# Qi_Lime_Pi_Rev_1.net
KiCad netlist of a schematic drawn in EAGLE
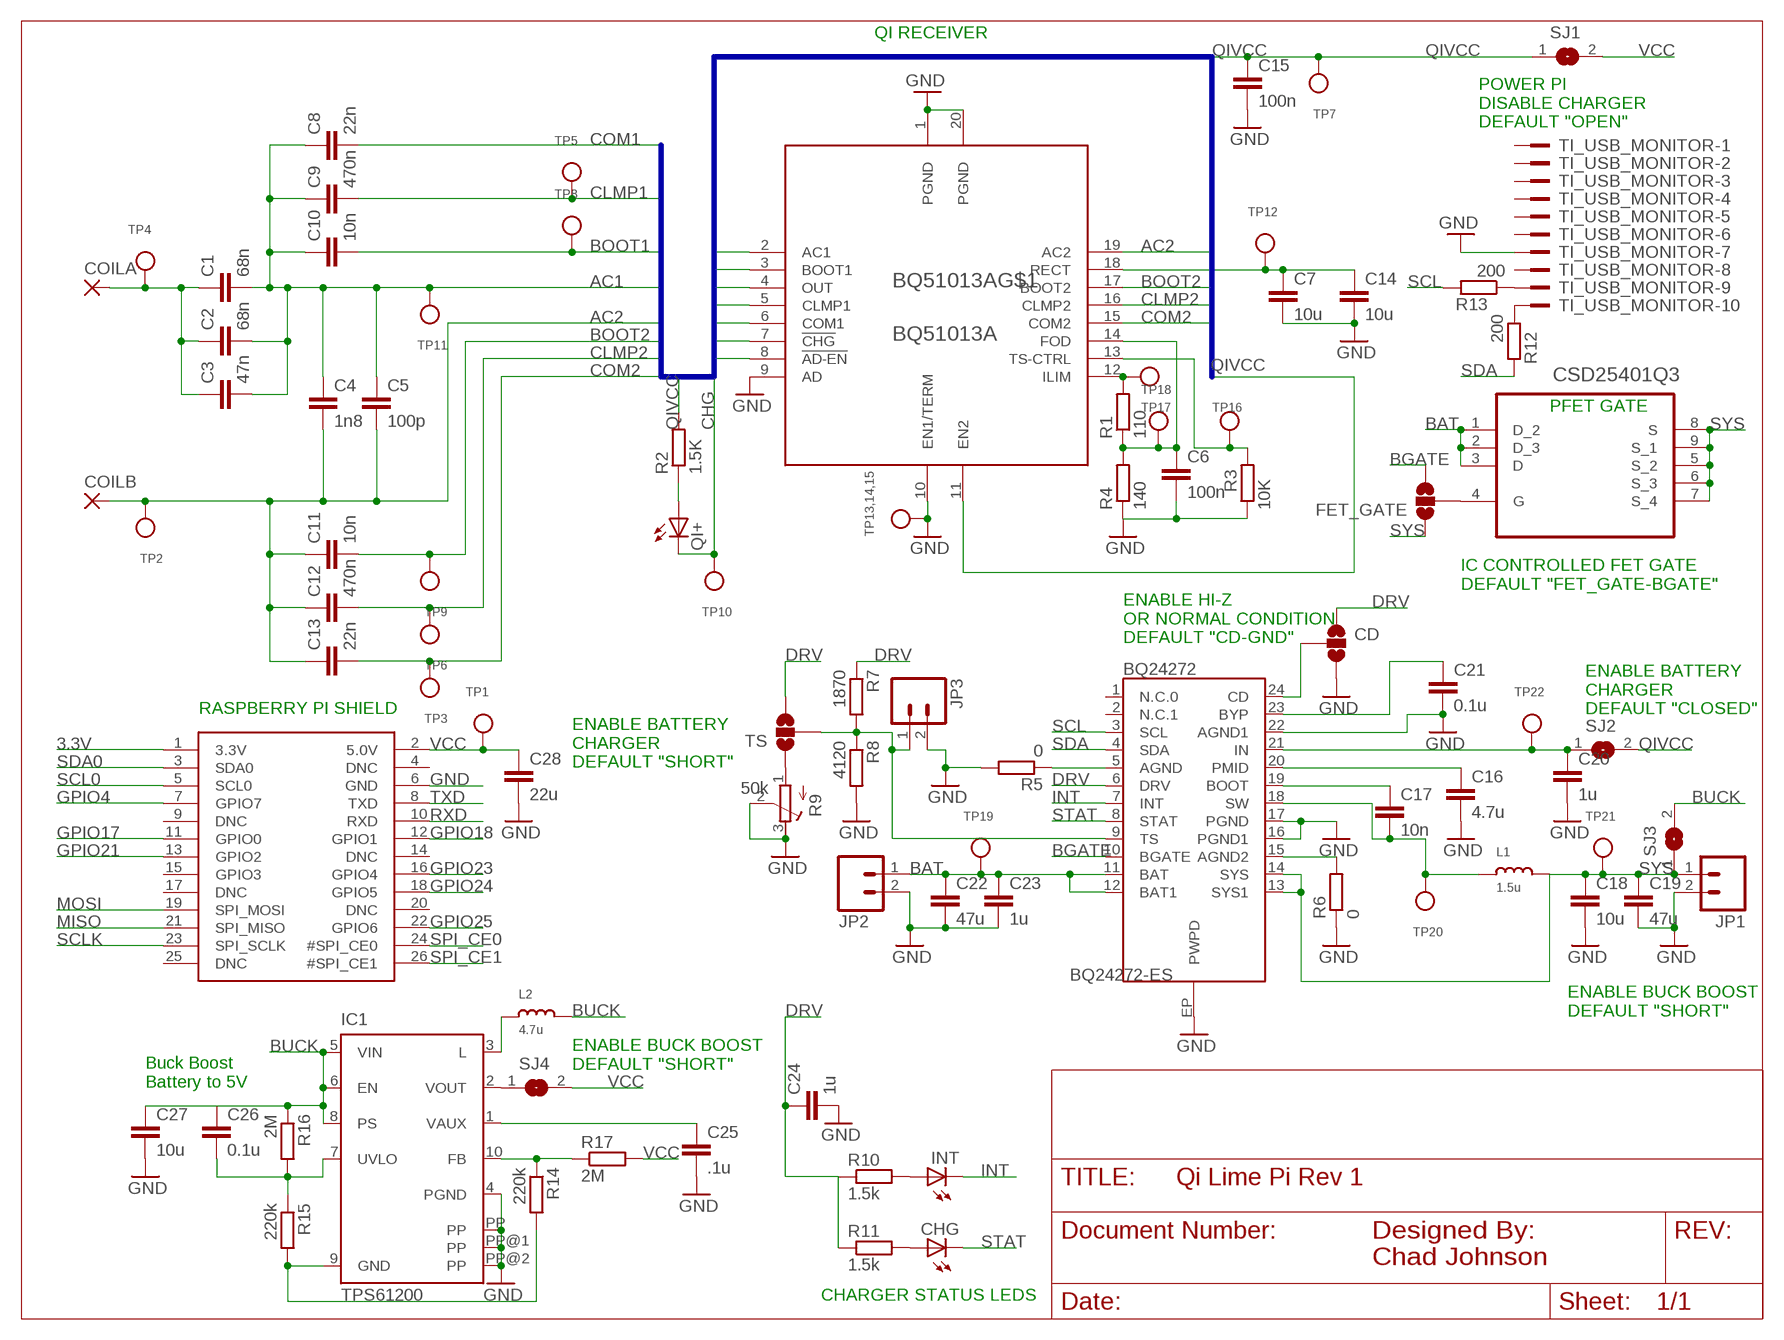
[diagram p0: schematic, sheet 1]

(export (version "E")
  (design (tool "Eeschema 10.0.6"))
  (components
    (comp (ref "BQ24272")
      (value "BQ24272-ES")
      (footprint "eagle-import:QFN-24_ALT2")
      (libsource (lib "eagle-import") (part "BQ24272-ES"))
    )
    (comp (ref "BQ51013A")
      (value "BQ51013A")
      (footprint "eagle-import:RHL_R-VQFN-N20")
      (libsource (lib "eagle-import") (part "BQ51013A"))
    )
    (comp (ref "C1")
      (value "68n")
      (footprint "eagle-import:C0603K")
      (fields (field (name "MF") "KEMET") (field (name "MPN") "C0603C682K5RACTU"))
      (libsource (lib "eagle-import") (part "C-EUC0603K"))
    )
    (comp (ref "C2")
      (value "68n")
      (footprint "eagle-import:C0603K")
      (fields (field (name "MF") "KEMET") (field (name "MPN") "C0603C682K5RACTU"))
      (libsource (lib "eagle-import") (part "C-EUC0603K"))
    )
    (comp (ref "C3")
      (value "47n")
      (footprint "eagle-import:C0603K")
      (fields (field (name "MPN") "C0603C473K5RACTU"))
      (libsource (lib "eagle-import") (part "C-EUC0603K"))
    )
    (comp (ref "C4")
      (value "1n8")
      (footprint "eagle-import:C0603K")
      (fields (field (name "MPN") "C0603C182K5RACTU"))
      (libsource (lib "eagle-import") (part "C-EUC0603K"))
    )
    (comp (ref "C5")
      (value "100p")
      (footprint "eagle-import:C0603K")
      (fields (field (name "MF") "KEMET") (field (name "MPN") "C0603C101K5RACTU"))
      (libsource (lib "eagle-import") (part "C-EUC0603K"))
    )
    (comp (ref "C6")
      (value "100n")
      (footprint "eagle-import:C0603K")
      (libsource (lib "eagle-import") (part "C-EUC0603K"))
    )
    (comp (ref "C7")
      (value "10u")
      (footprint "eagle-import:C0603K")
      (libsource (lib "eagle-import") (part "C-EUC0603K"))
    )
    (comp (ref "C8")
      (value "22n")
      (footprint "eagle-import:C0603K")
      (fields (field (name "MF") "KEMET") (field (name "MPN") "C0603C223K5RACTU"))
      (libsource (lib "eagle-import") (part "C-EUC0603K"))
    )
    (comp (ref "C9")
      (value "470n")
      (footprint "eagle-import:C0603K")
      (libsource (lib "eagle-import") (part "C-EUC0603K"))
    )
    (comp (ref "C10")
      (value "10n")
      (footprint "eagle-import:C0603K")
      (libsource (lib "eagle-import") (part "C-EUC0603K"))
    )
    (comp (ref "C11")
      (value "10n")
      (footprint "eagle-import:C0603K")
      (libsource (lib "eagle-import") (part "C-EUC0603K"))
    )
    (comp (ref "C12")
      (value "470n")
      (footprint "eagle-import:C0603K")
      (libsource (lib "eagle-import") (part "C-EUC0603K"))
    )
    (comp (ref "C13")
      (value "22n")
      (footprint "eagle-import:C0603K")
      (fields (field (name "MF") "KEMET") (field (name "MPN") "C0603C223K5RACTU"))
      (libsource (lib "eagle-import") (part "C-EUC0603K"))
    )
    (comp (ref "C14")
      (value "10u")
      (footprint "eagle-import:C0603K")
      (libsource (lib "eagle-import") (part "C-EUC0603K"))
    )
    (comp (ref "C15")
      (value "100n")
      (footprint "eagle-import:C0603K")
      (libsource (lib "eagle-import") (part "C-EUC0603K"))
    )
    (comp (ref "C16")
      (value "4.7u")
      (footprint "eagle-import:C0603K")
      (libsource (lib "eagle-import") (part "C-EUC0603K"))
    )
    (comp (ref "C17")
      (value "10n")
      (footprint "eagle-import:C0603K")
      (libsource (lib "eagle-import") (part "C-EUC0603K"))
    )
    (comp (ref "C18")
      (value "10u")
      (footprint "eagle-import:C0603K")
      (libsource (lib "eagle-import") (part "C-EUC0603K"))
    )
    (comp (ref "C19")
      (value "47u")
      (footprint "eagle-import:C0603K")
      (libsource (lib "eagle-import") (part "C-EUC0603K"))
    )
    (comp (ref "C20")
      (value "1u")
      (footprint "eagle-import:C0603K")
      (libsource (lib "eagle-import") (part "C-EUC0603K"))
    )
    (comp (ref "C21")
      (value "0.1u")
      (footprint "eagle-import:C0603K")
      (libsource (lib "eagle-import") (part "C-EUC0603K"))
    )
    (comp (ref "C22")
      (value "47u")
      (footprint "eagle-import:C0603K")
      (libsource (lib "eagle-import") (part "C-EUC0603K"))
    )
    (comp (ref "C23")
      (value "1u")
      (footprint "eagle-import:C0603K")
      (libsource (lib "eagle-import") (part "C-EUC0603K"))
    )
    (comp (ref "C24")
      (value "1u")
      (footprint "eagle-import:C0603K")
      (libsource (lib "eagle-import") (part "C-EUC0603K"))
    )
    (comp (ref "C25")
      (value ".1u")
      (footprint "eagle-import:C0603K")
      (libsource (lib "eagle-import") (part "C-EUC0603K"))
    )
    (comp (ref "C26")
      (value "0.1u")
      (footprint "eagle-import:C0603K")
      (libsource (lib "eagle-import") (part "C-EUC0603K"))
    )
    (comp (ref "C27")
      (value "10u")
      (footprint "eagle-import:C0603K")
      (libsource (lib "eagle-import") (part "C-EUC0603K"))
    )
    (comp (ref "C28")
      (value "22u")
      (footprint "eagle-import:C0603K")
      (libsource (lib "eagle-import") (part "C-EUC0603K"))
    )
    (comp (ref "CD")
      (value "SOLDERJUMPER_2WAYS")
      (footprint "eagle-import:SJ_3")
      (libsource (lib "eagle-import") (part "SOLDERJUMPER_2WAYS"))
    )
    (comp (ref "CHG")
      (value "LEDCHIP-LED0603")
      (footprint "eagle-import:CHIP-LED0603")
      (libsource (lib "eagle-import") (part "led_LEDCHIP-LED0603"))
    )
    (comp (ref "COILA")
      (value "1,6/0,8")
      (footprint "eagle-import:1,6_0,8")
      (libsource (lib "eagle-import") (part "1,6/0,8"))
    )
    (comp (ref "COILB")
      (value "1,6/0,8")
      (footprint "eagle-import:1,6_0,8")
      (libsource (lib "eagle-import") (part "1,6/0,8"))
    )
    (comp (ref "CSD25401Q3")
      (value "CSD25401Q3")
      (footprint "eagle-import:SON65P300X300X-9N")
      (libsource (lib "eagle-import") (part "CSD25401Q3"))
    )
    (comp (ref "FET_GATE")
      (value "SOLDERJUMPER_2WAYS")
      (footprint "eagle-import:SJ_3")
      (libsource (lib "eagle-import") (part "SOLDERJUMPER_2WAYS"))
    )
    (comp (ref "IC1")
      (value "TPS61200")
      (footprint "eagle-import:S-PDSO-N10")
      (fields (field (name "MPN") "TPS61200DRCT"))
      (libsource (lib "eagle-import") (part "TPS61200"))
    )
    (comp (ref "INT")
      (value "LEDCHIP-LED0603")
      (footprint "eagle-import:CHIP-LED0603")
      (libsource (lib "eagle-import") (part "led_LEDCHIP-LED0603"))
    )
    (comp (ref "JP1")
      (value "M02PTH3")
      (footprint "eagle-import:1X02_LONGPADS")
      (libsource (lib "eagle-import") (part "M02PTH3"))
    )
    (comp (ref "JP2")
      (value "M02PTH3")
      (footprint "eagle-import:1X02_LONGPADS")
      (libsource (lib "eagle-import") (part "M02PTH3"))
    )
    (comp (ref "JP3")
      (value "M02PTH3")
      (footprint "eagle-import:1X02_LONGPADS")
      (libsource (lib "eagle-import") (part "M02PTH3"))
    )
    (comp (ref "L1")
      (value "1.5u")
      (footprint "eagle-import:INDUCTOR_5X5MM_NR5040_NOTHERMALS")
      (libsource (lib "eagle-import") (part "INDUCTORNR5040"))
    )
    (comp (ref "L2")
      (value "4.7u")
      (footprint "eagle-import:INDUCTOR_5X5MM_NR5040_NOTHERMALS")
      (libsource (lib "eagle-import") (part "INDUCTORNR5040"))
    )
    (comp (ref "QI+")
      (value "LEDCHIP-LED0603")
      (footprint "eagle-import:CHIP-LED0603")
      (libsource (lib "eagle-import") (part "LEDCHIP-LED0603"))
    )
    (comp (ref "R1")
      (value "110")
      (footprint "eagle-import:R0402")
      (fields (field (name "MPN") "ERJ3EKF3000V"))
      (libsource (lib "eagle-import") (part "R-EU_R0402"))
    )
    (comp (ref "R2")
      (value "1.5K")
      (footprint "eagle-import:R0402")
      (fields (field (name "MPN") "ERJ3EKF3000V"))
      (libsource (lib "eagle-import") (part "R-EU_R0402"))
    )
    (comp (ref "R3")
      (value "10K")
      (footprint "eagle-import:R0402")
      (fields (field (name "MPN") "ERJ3EKF3000V"))
      (libsource (lib "eagle-import") (part "R-EU_R0402"))
    )
    (comp (ref "R4")
      (value "140")
      (footprint "eagle-import:R0402")
      (fields (field (name "MPN") "ERJ3EKF3000V"))
      (libsource (lib "eagle-import") (part "R-EU_R0402"))
    )
    (comp (ref "R5")
      (value "0")
      (footprint "eagle-import:R0402")
      (fields (field (name "MPN") "ERJ3EKF3000V"))
      (libsource (lib "eagle-import") (part "R-EU_R0402"))
    )
    (comp (ref "R6")
      (value "0")
      (footprint "eagle-import:R0402")
      (fields (field (name "MPN") "ERJ3EKF3000V"))
      (libsource (lib "eagle-import") (part "R-EU_R0402"))
    )
    (comp (ref "R7")
      (value "1870")
      (footprint "eagle-import:R0402")
      (fields (field (name "MPN") "ERJ3EKF3000V"))
      (libsource (lib "eagle-import") (part "R-EU_R0402"))
    )
    (comp (ref "R8")
      (value "4120")
      (footprint "eagle-import:R0402")
      (fields (field (name "MPN") "ERJ3EKF3000V"))
      (libsource (lib "eagle-import") (part "R-EU_R0402"))
    )
    (comp (ref "R9")
      (value "50k")
      (footprint "eagle-import:RTRIM64Y")
      (libsource (lib "eagle-import") (part "R-TRIMM64Y"))
    )
    (comp (ref "R10")
      (value "1.5k")
      (footprint "eagle-import:R0402")
      (fields (field (name "MPN") "ERJ3EKF3000V"))
      (libsource (lib "eagle-import") (part "R-EU_R0402"))
    )
    (comp (ref "R11")
      (value "1.5k")
      (footprint "eagle-import:R0402")
      (fields (field (name "MPN") "ERJ3EKF3000V"))
      (libsource (lib "eagle-import") (part "R-EU_R0402"))
    )
    (comp (ref "R12")
      (value "200")
      (footprint "eagle-import:R0402")
      (fields (field (name "MPN") "ERJ3EKF3000V"))
      (libsource (lib "eagle-import") (part "R-EU_R0402"))
    )
    (comp (ref "R13")
      (value "200")
      (footprint "eagle-import:R0402")
      (fields (field (name "MPN") "ERJ3EKF3000V"))
      (libsource (lib "eagle-import") (part "R-EU_R0402"))
    )
    (comp (ref "R14")
      (value "220k")
      (footprint "eagle-import:R0402")
      (fields (field (name "MPN") "ERJ3EKF3000V"))
      (libsource (lib "eagle-import") (part "R-EU_R0402"))
    )
    (comp (ref "R15")
      (value "220k")
      (footprint "eagle-import:R0402")
      (fields (field (name "MPN") "ERJ3EKF3000V"))
      (libsource (lib "eagle-import") (part "R-EU_R0402"))
    )
    (comp (ref "R16")
      (value "2M")
      (footprint "eagle-import:R0402")
      (fields (field (name "MPN") "ERJ3EKF3000V"))
      (libsource (lib "eagle-import") (part "R-EU_R0402"))
    )
    (comp (ref "R17")
      (value "2M")
      (footprint "eagle-import:R0402")
      (fields (field (name "MPN") "ERJ3EKF3000V"))
      (libsource (lib "eagle-import") (part "R-EU_R0402"))
    )
    (comp (ref "SJ1") (value "SJ") (footprint "eagle-import:SJ") (libsource (lib "eagle-import") (part "SJ")))
    (comp (ref "SJ2") (value "SJ") (footprint "eagle-import:SJ") (libsource (lib "eagle-import") (part "SJ")))
    (comp (ref "SJ3") (value "SJ") (footprint "eagle-import:SJ") (libsource (lib "eagle-import") (part "SJ")))
    (comp (ref "SJ4") (value "SJ") (footprint "eagle-import:SJ") (libsource (lib "eagle-import") (part "SJ")))
    (comp (ref "TI_USB_MONITOR")
      (value "2510-")
      (footprint "eagle-import:PAK100_2500-10")
      (fields (field (name "MF") "3M") (field (name "MPN") "2510-6002UB"))
      (libsource (lib "eagle-import") (part "2510-"))
    )
    (comp (ref "TP1")
      (value "TESTPOINTROUND1MM")
      (footprint "eagle-import:TESTPOINT_ROUND_1MM")
      (libsource (lib "eagle-import") (part "TESTPOINTROUND1MM"))
    )
    (comp (ref "TP2")
      (value "TESTPOINTROUND1MM")
      (footprint "eagle-import:TESTPOINT_ROUND_1MM")
      (libsource (lib "eagle-import") (part "TESTPOINTROUND1MM"))
    )
    (comp (ref "TP3")
      (value "TESTPOINTROUND1MM")
      (footprint "eagle-import:TESTPOINT_ROUND_1MM")
      (libsource (lib "eagle-import") (part "TESTPOINTROUND1MM"))
    )
    (comp (ref "TP4")
      (value "TESTPOINTROUND1MM")
      (footprint "eagle-import:TESTPOINT_ROUND_1MM")
      (libsource (lib "eagle-import") (part "TESTPOINTROUND1MM"))
    )
    (comp (ref "TP5")
      (value "TESTPOINTROUND1MM")
      (footprint "eagle-import:TESTPOINT_ROUND_1MM")
      (libsource (lib "eagle-import") (part "TESTPOINTROUND1MM"))
    )
    (comp (ref "TP6")
      (value "TESTPOINTROUND1MM")
      (footprint "eagle-import:TESTPOINT_ROUND_1MM")
      (libsource (lib "eagle-import") (part "TESTPOINTROUND1MM"))
    )
    (comp (ref "TP7")
      (value "TESTPOINTROUND1MM")
      (footprint "eagle-import:TESTPOINT_ROUND_1MM")
      (libsource (lib "eagle-import") (part "TESTPOINTROUND1MM"))
    )
    (comp (ref "TP8")
      (value "TESTPOINTROUND1MM")
      (footprint "eagle-import:TESTPOINT_ROUND_1MM")
      (libsource (lib "eagle-import") (part "TESTPOINTROUND1MM"))
    )
    (comp (ref "TP9")
      (value "TESTPOINTROUND1MM")
      (footprint "eagle-import:TESTPOINT_ROUND_1MM")
      (libsource (lib "eagle-import") (part "TESTPOINTROUND1MM"))
    )
    (comp (ref "TP10")
      (value "TESTPOINTROUND1MM")
      (footprint "eagle-import:TESTPOINT_ROUND_1MM")
      (libsource (lib "eagle-import") (part "TESTPOINTROUND1MM"))
    )
    (comp (ref "TP11")
      (value "TESTPOINTROUND1MM")
      (footprint "eagle-import:TESTPOINT_ROUND_1MM")
      (libsource (lib "eagle-import") (part "TESTPOINTROUND1MM"))
    )
    (comp (ref "TP12")
      (value "TESTPOINTROUND1MM")
      (footprint "eagle-import:TESTPOINT_ROUND_1MM")
      (libsource (lib "eagle-import") (part "TESTPOINTROUND1MM"))
    )
    (comp (ref "TP13,14,15")
      (value "TESTPOINTROUND1MM")
      (footprint "eagle-import:TESTPOINT_ROUND_1MM")
      (libsource (lib "eagle-import") (part "TESTPOINTROUND1MM"))
    )
    (comp (ref "TP16")
      (value "TESTPOINTROUND1MM")
      (footprint "eagle-import:TESTPOINT_ROUND_1MM")
      (libsource (lib "eagle-import") (part "TESTPOINTROUND1MM"))
    )
    (comp (ref "TP17")
      (value "TESTPOINTROUND1MM")
      (footprint "eagle-import:TESTPOINT_ROUND_1MM")
      (libsource (lib "eagle-import") (part "TESTPOINTROUND1MM"))
    )
    (comp (ref "TP18")
      (value "TESTPOINTROUND1MM")
      (footprint "eagle-import:TESTPOINT_ROUND_1MM")
      (libsource (lib "eagle-import") (part "TESTPOINTROUND1MM"))
    )
    (comp (ref "TP19")
      (value "TESTPOINTROUND1MM")
      (footprint "eagle-import:TESTPOINT_ROUND_1MM")
      (libsource (lib "eagle-import") (part "TESTPOINTROUND1MM"))
    )
    (comp (ref "TP20")
      (value "TESTPOINTROUND1MM")
      (footprint "eagle-import:TESTPOINT_ROUND_1MM")
      (libsource (lib "eagle-import") (part "TESTPOINTROUND1MM"))
    )
    (comp (ref "TP21")
      (value "TESTPOINTROUND1MM")
      (footprint "eagle-import:TESTPOINT_ROUND_1MM")
      (libsource (lib "eagle-import") (part "TESTPOINTROUND1MM"))
    )
    (comp (ref "TP22")
      (value "TESTPOINTROUND1MM")
      (footprint "eagle-import:TESTPOINT_ROUND_1MM")
      (libsource (lib "eagle-import") (part "TESTPOINTROUND1MM"))
    )
    (comp (ref "TS")
      (value "SOLDERJUMPER_2WAYS")
      (footprint "eagle-import:SJ_3")
      (libsource (lib "eagle-import") (part "SOLDERJUMPER_2WAYS"))
    )
    (comp (ref "U$1")
      (value "RASPBERRYPI_BB")
      (footprint "eagle-import:RASBERRYPI_SHIELD")
      (libsource (lib "eagle-import") (part "RASPBERRYPI_BB"))
    )
  )
  (nets
    (net (code "1") (name "/3.3V") (class "Default")
      (node (ref "U$1") (pin "1") (pinfunction "3.3V_1") (pintype "power_in"))
    )
    (net (code "2") (name "/AC1") (class "Default")
      (node (ref "BQ51013A") (pin "2") (pinfunction "AC1_2") (pintype "bidirectional"))
      (node (ref "C1") (pin "2") (pinfunction "2_2") (pintype "passive"))
      (node (ref "C10") (pin "1") (pinfunction "1_1") (pintype "passive"))
      (node (ref "C2") (pin "2") (pinfunction "2_2") (pintype "passive"))
      (node (ref "C3") (pin "2") (pinfunction "2_2") (pintype "passive"))
      (node (ref "C4") (pin "1") (pinfunction "1_1") (pintype "passive"))
      (node (ref "C5") (pin "1") (pinfunction "1_1") (pintype "passive"))
      (node (ref "C8") (pin "1") (pinfunction "1_1") (pintype "passive"))
      (node (ref "C9") (pin "1") (pinfunction "1_1") (pintype "passive"))
      (node (ref "TP11") (pin "P$1") (pinfunction "P$1_P$1") (pintype "bidirectional"))
    )
    (net (code "3") (name "/AC2") (class "Default")
      (node (ref "BQ51013A") (pin "19") (pinfunction "AC2_19") (pintype "bidirectional"))
      (node (ref "C11") (pin "1") (pinfunction "1_1") (pintype "passive"))
      (node (ref "C12") (pin "1") (pinfunction "1_1") (pintype "passive"))
      (node (ref "C13") (pin "1") (pinfunction "1_1") (pintype "passive"))
      (node (ref "C4") (pin "2") (pinfunction "2_2") (pintype "passive"))
      (node (ref "C5") (pin "2") (pinfunction "2_2") (pintype "passive"))
      (node (ref "COILB") (pin "1") (pinfunction "P_1") (pintype "passive"))
      (node (ref "TP2") (pin "P$1") (pinfunction "P$1_P$1") (pintype "bidirectional"))
    )
    (net (code "4") (name "/BAT") (class "Default")
      (node (ref "BQ24272") (pin "11") (pinfunction "BAT_11") (pintype "bidirectional"))
      (node (ref "BQ24272") (pin "12") (pinfunction "BAT1_12") (pintype "bidirectional"))
      (node (ref "C22") (pin "1") (pinfunction "1_1") (pintype "passive"))
      (node (ref "C23") (pin "1") (pinfunction "1_1") (pintype "passive"))
      (node (ref "CSD25401Q3") (pin "1") (pinfunction "D_2_1") (pintype "passive"))
      (node (ref "CSD25401Q3") (pin "2") (pinfunction "D_3_2") (pintype "passive"))
      (node (ref "CSD25401Q3") (pin "3") (pinfunction "D_3") (pintype "passive"))
      (node (ref "JP2") (pin "1") (pinfunction "1_1") (pintype "passive"))
      (node (ref "TP19") (pin "P$1") (pinfunction "P$1_P$1") (pintype "bidirectional"))
    )
    (net (code "5") (name "/BGATE") (class "Default")
      (node (ref "BQ24272") (pin "10") (pinfunction "BGATE_10") (pintype "bidirectional"))
      (node (ref "FET_GATE") (pin "3") (pinfunction "3_3") (pintype "passive"))
    )
    (net (code "6") (name "/BOOT1") (class "Default")
      (node (ref "BQ51013A") (pin "3") (pinfunction "BOOT1_3") (pintype "bidirectional"))
      (node (ref "C10") (pin "2") (pinfunction "2_2") (pintype "passive"))
      (node (ref "TP8") (pin "P$1") (pinfunction "P$1_P$1") (pintype "bidirectional"))
    )
    (net (code "7") (name "/BOOT2") (class "Default")
      (node (ref "BQ51013A") (pin "17") (pinfunction "BOOT2_17") (pintype "bidirectional"))
      (node (ref "C11") (pin "2") (pinfunction "2_2") (pintype "passive"))
      (node (ref "TP9") (pin "P$1") (pinfunction "P$1_P$1") (pintype "bidirectional"))
    )
    (net (code "8") (name "/BUCK") (class "Default")
      (node (ref "C26") (pin "1") (pinfunction "1_1") (pintype "passive"))
      (node (ref "C27") (pin "1") (pinfunction "1_1") (pintype "passive"))
      (node (ref "IC1") (pin "5") (pinfunction "VIN_5") (pintype "input"))
      (node (ref "IC1") (pin "6") (pinfunction "EN_6") (pintype "input"))
      (node (ref "IC1") (pin "8") (pinfunction "PS_8") (pintype "input"))
      (node (ref "L2") (pin "P$2") (pinfunction "2_P$2") (pintype "passive"))
      (node (ref "R16") (pin "1") (pinfunction "1_1") (pintype "passive"))
      (node (ref "SJ3") (pin "2") (pinfunction "2_2") (pintype "passive"))
    )
    (net (code "9") (name "/CHG") (class "Default")
      (node (ref "BQ51013A") (pin "7") (pinfunction "~{CHG}_7") (pintype "bidirectional"))
      (node (ref "QI+") (pin "C") (pinfunction "C_C") (pintype "passive"))
      (node (ref "TP10") (pin "P$1") (pinfunction "P$1_P$1") (pintype "bidirectional"))
    )
    (net (code "10") (name "/CLMP1") (class "Default")
      (node (ref "BQ51013A") (pin "5") (pinfunction "CLMP1_5") (pintype "bidirectional"))
      (node (ref "C9") (pin "2") (pinfunction "2_2") (pintype "passive"))
      (node (ref "TP5") (pin "P$1") (pinfunction "P$1_P$1") (pintype "bidirectional"))
    )
    (net (code "11") (name "/CLMP2") (class "Default")
      (node (ref "BQ51013A") (pin "16") (pinfunction "CLMP2_16") (pintype "bidirectional"))
      (node (ref "C12") (pin "2") (pinfunction "2_2") (pintype "passive"))
      (node (ref "TP6") (pin "P$1") (pinfunction "P$1_P$1") (pintype "bidirectional"))
    )
    (net (code "12") (name "/COM1") (class "Default")
      (node (ref "BQ51013A") (pin "6") (pinfunction "COM1_6") (pintype "bidirectional"))
      (node (ref "C8") (pin "2") (pinfunction "2_2") (pintype "passive"))
    )
    (net (code "13") (name "/COM2") (class "Default")
      (node (ref "BQ51013A") (pin "15") (pinfunction "COM2_15") (pintype "bidirectional"))
      (node (ref "C13") (pin "2") (pinfunction "2_2") (pintype "passive"))
      (node (ref "TP3") (pin "P$1") (pinfunction "P$1_P$1") (pintype "bidirectional"))
    )
    (net (code "14") (name "/DRV") (class "Default")
      (node (ref "BQ24272") (pin "6") (pinfunction "DRV_6") (pintype "bidirectional"))
      (node (ref "C24") (pin "1") (pinfunction "1_1") (pintype "passive"))
      (node (ref "CD") (pin "1") (pinfunction "1_1") (pintype "passive"))
      (node (ref "R10") (pin "1") (pinfunction "1_1") (pintype "passive"))
      (node (ref "R11") (pin "1") (pinfunction "1_1") (pintype "passive"))
      (node (ref "R7") (pin "1") (pinfunction "1_1") (pintype "passive"))
      (node (ref "TS") (pin "3") (pinfunction "3_3") (pintype "passive"))
    )
    (net (code "15") (name "/GPIO4") (class "Default")
      (node (ref "U$1") (pin "7") (pinfunction "GPIO7_7") (pintype "bidirectional"))
    )
    (net (code "16") (name "/GPIO17") (class "Default")
      (node (ref "U$1") (pin "11") (pinfunction "GPIO0_11") (pintype "bidirectional"))
    )
    (net (code "17") (name "/GPIO18") (class "Default")
      (node (ref "U$1") (pin "12") (pinfunction "GPIO1_12") (pintype "bidirectional"))
    )
    (net (code "18") (name "/GPIO21") (class "Default")
      (node (ref "U$1") (pin "13") (pinfunction "GPIO2_13") (pintype "bidirectional"))
    )
    (net (code "19") (name "/GPIO23") (class "Default")
      (node (ref "U$1") (pin "16") (pinfunction "GPIO4_16") (pintype "bidirectional"))
    )
    (net (code "20") (name "/GPIO24") (class "Default")
      (node (ref "U$1") (pin "18") (pinfunction "GPIO5_18") (pintype "bidirectional"))
    )
    (net (code "21") (name "/GPIO25") (class "Default")
      (node (ref "U$1") (pin "22") (pinfunction "GPIO6_22") (pintype "bidirectional"))
    )
    (net (code "22") (name "/INT") (class "Default")
      (node (ref "BQ24272") (pin "7") (pinfunction "INT_7") (pintype "bidirectional"))
      (node (ref "INT") (pin "C") (pinfunction "C_C") (pintype "passive"))
    )
    (net (code "23") (name "/MISO") (class "Default")
      (node (ref "U$1") (pin "21") (pinfunction "SPI_MISO_21") (pintype "input"))
    )
    (net (code "24") (name "/MOSI") (class "Default")
      (node (ref "U$1") (pin "19") (pinfunction "SPI_MOSI_19") (pintype "output"))
    )
    (net (code "25") (name "/QIVCC") (class "Default")
      (node (ref "BQ51013A") (pin "11") (pinfunction "EN2_11") (pintype "bidirectional"))
      (node (ref "BQ51013A") (pin "4") (pinfunction "OUT_4") (pintype "bidirectional"))
      (node (ref "C15") (pin "1") (pinfunction "1_1") (pintype "passive"))
      (node (ref "R2") (pin "2") (pinfunction "2_2") (pintype "passive"))
      (node (ref "SJ1") (pin "1") (pinfunction "1_1") (pintype "passive"))
      (node (ref "SJ2") (pin "2") (pinfunction "2_2") (pintype "passive"))
      (node (ref "TP7") (pin "P$1") (pinfunction "P$1_P$1") (pintype "bidirectional"))
    )
    (net (code "26") (name "/RECT") (class "Default")
      (node (ref "BQ51013A") (pin "18") (pinfunction "RECT_18") (pintype "bidirectional"))
      (node (ref "C14") (pin "1") (pinfunction "1_1") (pintype "passive"))
      (node (ref "C7") (pin "1") (pinfunction "1_1") (pintype "passive"))
      (node (ref "TP12") (pin "P$1") (pinfunction "P$1_P$1") (pintype "bidirectional"))
    )
    (net (code "27") (name "/RXD") (class "Default")
      (node (ref "U$1") (pin "10") (pinfunction "RXD_10") (pintype "input"))
    )
    (net (code "28") (name "/SCL") (class "Default")
      (node (ref "BQ24272") (pin "3") (pinfunction "SCL_3") (pintype "bidirectional"))
      (node (ref "R13") (pin "2") (pinfunction "2_2") (pintype "passive"))
    )
    (net (code "29") (name "/SCL0") (class "Default")
      (node (ref "U$1") (pin "5") (pinfunction "SCL0_5") (pintype "output"))
    )
    (net (code "30") (name "/SCLK") (class "Default")
      (node (ref "U$1") (pin "23") (pinfunction "SPI_SCLK_23") (pintype "output"))
    )
    (net (code "31") (name "/SDA") (class "Default")
      (node (ref "BQ24272") (pin "4") (pinfunction "SDA_4") (pintype "bidirectional"))
      (node (ref "R12") (pin "2") (pinfunction "2_2") (pintype "passive"))
    )
    (net (code "32") (name "/SDA0") (class "Default")
      (node (ref "U$1") (pin "3") (pinfunction "SDA0_3") (pintype "bidirectional"))
    )
    (net (code "33") (name "/SPI_CE0") (class "Default")
      (node (ref "U$1") (pin "24") (pinfunction "#SPI_CE0_24") (pintype "output"))
    )
    (net (code "34") (name "/SPI_CE1") (class "Default")
      (node (ref "U$1") (pin "26") (pinfunction "#SPI_CE1_26") (pintype "output"))
    )
    (net (code "35") (name "/STAT") (class "Default")
      (node (ref "BQ24272") (pin "8") (pinfunction "STAT_8") (pintype "bidirectional"))
      (node (ref "CHG") (pin "C") (pinfunction "C_C") (pintype "passive"))
    )
    (net (code "36") (name "/SYS") (class "Default")
      (node (ref "BQ24272") (pin "13") (pinfunction "SYS1_13") (pintype "bidirectional"))
      (node (ref "BQ24272") (pin "14") (pinfunction "SYS_14") (pintype "bidirectional"))
      (node (ref "C18") (pin "1") (pinfunction "1_1") (pintype "passive"))
      (node (ref "C19") (pin "1") (pinfunction "1_1") (pintype "passive"))
      (node (ref "CSD25401Q3") (pin "5") (pinfunction "S_2_5") (pintype "passive"))
      (node (ref "CSD25401Q3") (pin "6") (pinfunction "S_3_6") (pintype "passive"))
      (node (ref "CSD25401Q3") (pin "7") (pinfunction "S_4_7") (pintype "passive"))
      (node (ref "CSD25401Q3") (pin "8") (pinfunction "S_8") (pintype "passive"))
      (node (ref "CSD25401Q3") (pin "9") (pinfunction "S_1_9") (pintype "passive"))
      (node (ref "FET_GATE") (pin "1") (pinfunction "1_1") (pintype "passive"))
      (node (ref "JP1") (pin "1") (pinfunction "1_1") (pintype "passive"))
      (node (ref "L1") (pin "P$2") (pinfunction "2_P$2") (pintype "passive"))
      (node (ref "SJ3") (pin "1") (pinfunction "1_1") (pintype "passive"))
      (node (ref "TP21") (pin "P$1") (pinfunction "P$1_P$1") (pintype "bidirectional"))
    )
    (net (code "37") (name "/TXD") (class "Default")
      (node (ref "U$1") (pin "8") (pinfunction "TXD_8") (pintype "output"))
    )
    (net (code "38") (name "/VCC") (class "Default")
      (node (ref "C28") (pin "1") (pinfunction "1_1") (pintype "passive"))
      (node (ref "R17") (pin "2") (pinfunction "2_2") (pintype "passive"))
      (node (ref "SJ1") (pin "2") (pinfunction "2_2") (pintype "passive"))
      (node (ref "SJ4") (pin "2") (pinfunction "2_2") (pintype "passive"))
      (node (ref "TP1") (pin "P$1") (pinfunction "P$1_P$1") (pintype "bidirectional"))
      (node (ref "U$1") (pin "2") (pinfunction "5.0V_2") (pintype "power_in"))
    )
    (net (code "39") (name "GND") (class "Default")
      (node (ref "BQ24272") (pin "16") (pinfunction "PGND1_16") (pintype "bidirectional"))
      (node (ref "BQ24272") (pin "17") (pinfunction "PGND_17") (pintype "bidirectional"))
      (node (ref "BQ24272") (pin "22") (pinfunction "AGND1_22") (pintype "bidirectional"))
      (node (ref "BQ24272") (pin "EP") (pinfunction "PWPD_EP") (pintype "bidirectional"))
      (node (ref "BQ51013A") (pin "1") (pinfunction "PGND_1") (pintype "bidirectional"))
      (node (ref "BQ51013A") (pin "10") (pinfunction "EN1/TERM_10") (pintype "bidirectional"))
      (node (ref "BQ51013A") (pin "20") (pinfunction "PGND_20") (pintype "bidirectional"))
      (node (ref "BQ51013A") (pin "9") (pinfunction "AD_9") (pintype "bidirectional"))
      (node (ref "C14") (pin "2") (pinfunction "2_2") (pintype "passive"))
      (node (ref "C15") (pin "2") (pinfunction "2_2") (pintype "passive"))
      (node (ref "C16") (pin "2") (pinfunction "2_2") (pintype "passive"))
      (node (ref "C18") (pin "2") (pinfunction "2_2") (pintype "passive"))
      (node (ref "C19") (pin "2") (pinfunction "2_2") (pintype "passive"))
      (node (ref "C20") (pin "2") (pinfunction "2_2") (pintype "passive"))
      (node (ref "C21") (pin "2") (pinfunction "2_2") (pintype "passive"))
      (node (ref "C22") (pin "2") (pinfunction "2_2") (pintype "passive"))
      (node (ref "C23") (pin "2") (pinfunction "2_2") (pintype "passive"))
      (node (ref "C24") (pin "2") (pinfunction "2_2") (pintype "passive"))
      (node (ref "C25") (pin "2") (pinfunction "2_2") (pintype "passive"))
      (node (ref "C27") (pin "2") (pinfunction "2_2") (pintype "passive"))
      (node (ref "C28") (pin "2") (pinfunction "2_2") (pintype "passive"))
      (node (ref "C6") (pin "2") (pinfunction "2_2") (pintype "passive"))
      (node (ref "C7") (pin "2") (pinfunction "2_2") (pintype "passive"))
      (node (ref "CD") (pin "3") (pinfunction "3_3") (pintype "passive"))
      (node (ref "IC1") (pin "4") (pinfunction "PGND_4") (pintype "power_in"))
      (node (ref "IC1") (pin "PP") (pinfunction "PP_PP") (pintype "power_in"))
      (node (ref "IC1") (pin "PP@1") (pinfunction "PP_PP@1") (pintype "power_in"))
      (node (ref "IC1") (pin "PP@2") (pinfunction "PP_PP@2") (pintype "power_in"))
      (node (ref "JP1") (pin "2") (pinfunction "2_2") (pintype "passive"))
      (node (ref "JP2") (pin "2") (pinfunction "2_2") (pintype "passive"))
      (node (ref "JP3") (pin "2") (pinfunction "2_2") (pintype "passive"))
      (node (ref "R3") (pin "1") (pinfunction "1_1") (pintype "passive"))
      (node (ref "R4") (pin "1") (pinfunction "1_1") (pintype "passive"))
      (node (ref "R5") (pin "2") (pinfunction "2_2") (pintype "passive"))
      (node (ref "R6") (pin "1") (pinfunction "1_1") (pintype "passive"))
      (node (ref "R8") (pin "2") (pinfunction "2_2") (pintype "passive"))
      (node (ref "R9") (pin "2") (pinfunction "S_2") (pintype "passive"))
      (node (ref "R9") (pin "3") (pinfunction "E_3") (pintype "passive"))
      (node (ref "TI_USB_MONITOR") (pin "7") (pinfunction "KL_7") (pintype "passive"))
      (node (ref "TP13,14,15") (pin "P$1") (pinfunction "P$1_P$1") (pintype "bidirectional"))
      (node (ref "U$1") (pin "6") (pinfunction "GND_6") (pintype "power_in"))
    )
    (net (code "40") (name "Net-(BQ24272-AGND)") (class "Default")
      (node (ref "BQ24272") (pin "5") (pinfunction "AGND_5") (pintype "bidirectional"))
      (node (ref "R5") (pin "1") (pinfunction "1_1") (pintype "passive"))
    )
    (net (code "41") (name "Net-(BQ24272-AGND2)") (class "Default")
      (node (ref "BQ24272") (pin "15") (pinfunction "AGND2_15") (pintype "bidirectional"))
      (node (ref "R6") (pin "2") (pinfunction "2_2") (pintype "passive"))
    )
    (net (code "42") (name "Net-(BQ24272-BOOT)") (class "Default")
      (node (ref "BQ24272") (pin "19") (pinfunction "BOOT_19") (pintype "bidirectional"))
      (node (ref "C17") (pin "1") (pinfunction "1_1") (pintype "passive"))
    )
    (net (code "43") (name "Net-(BQ24272-BYP)") (class "Default")
      (node (ref "BQ24272") (pin "23") (pinfunction "BYP_23") (pintype "bidirectional"))
      (node (ref "C21") (pin "1") (pinfunction "1_1") (pintype "passive"))
    )
    (net (code "44") (name "Net-(BQ24272-CD)") (class "Default")
      (node (ref "BQ24272") (pin "24") (pinfunction "CD_24") (pintype "bidirectional"))
      (node (ref "CD") (pin "2") (pinfunction "2_2") (pintype "passive"))
    )
    (net (code "45") (name "Net-(BQ24272-IN)") (class "Default")
      (node (ref "BQ24272") (pin "21") (pinfunction "IN_21") (pintype "bidirectional"))
      (node (ref "C20") (pin "1") (pinfunction "1_1") (pintype "passive"))
      (node (ref "SJ2") (pin "1") (pinfunction "1_1") (pintype "passive"))
      (node (ref "TP22") (pin "P$1") (pinfunction "P$1_P$1") (pintype "bidirectional"))
    )
    (net (code "46") (name "Net-(BQ24272-PMID)") (class "Default")
      (node (ref "BQ24272") (pin "20") (pinfunction "PMID_20") (pintype "bidirectional"))
      (node (ref "C16") (pin "1") (pinfunction "1_1") (pintype "passive"))
    )
    (net (code "47") (name "Net-(BQ24272-SW)") (class "Default")
      (node (ref "BQ24272") (pin "18") (pinfunction "SW_18") (pintype "bidirectional"))
      (node (ref "C17") (pin "2") (pinfunction "2_2") (pintype "passive"))
      (node (ref "L1") (pin "P$1") (pinfunction "1_P$1") (pintype "passive"))
      (node (ref "TP20") (pin "P$1") (pinfunction "P$1_P$1") (pintype "bidirectional"))
    )
    (net (code "48") (name "Net-(BQ24272-TS)") (class "Default")
      (node (ref "BQ24272") (pin "9") (pinfunction "TS_9") (pintype "bidirectional"))
      (node (ref "JP3") (pin "1") (pinfunction "1_1") (pintype "passive"))
      (node (ref "R7") (pin "2") (pinfunction "2_2") (pintype "passive"))
      (node (ref "R8") (pin "1") (pinfunction "1_1") (pintype "passive"))
      (node (ref "TS") (pin "2") (pinfunction "2_2") (pintype "passive"))
    )
    (net (code "49") (name "Net-(BQ51013AA-FOD)") (class "Default")
      (node (ref "BQ51013A") (pin "14") (pinfunction "FOD_14") (pintype "bidirectional"))
      (node (ref "C6") (pin "1") (pinfunction "1_1") (pintype "passive"))
      (node (ref "R1") (pin "1") (pinfunction "1_1") (pintype "passive"))
      (node (ref "R4") (pin "2") (pinfunction "2_2") (pintype "passive"))
      (node (ref "TP17") (pin "P$1") (pinfunction "P$1_P$1") (pintype "bidirectional"))
    )
    (net (code "50") (name "Net-(BQ51013AA-ILIM)") (class "Default")
      (node (ref "BQ51013A") (pin "12") (pinfunction "ILIM_12") (pintype "bidirectional"))
      (node (ref "R1") (pin "2") (pinfunction "2_2") (pintype "passive"))
      (node (ref "TP18") (pin "P$1") (pinfunction "P$1_P$1") (pintype "bidirectional"))
    )
    (net (code "51") (name "Net-(BQ51013AA-TS-CTRL)") (class "Default")
      (node (ref "BQ51013A") (pin "13") (pinfunction "TS-CTRL_13") (pintype "bidirectional"))
      (node (ref "R3") (pin "2") (pinfunction "2_2") (pintype "passive"))
      (node (ref "TP16") (pin "P$1") (pinfunction "P$1_P$1") (pintype "bidirectional"))
    )
    (net (code "52") (name "Net-(CHG-PadA)") (class "Default")
      (node (ref "CHG") (pin "A") (pinfunction "A_A") (pintype "passive"))
      (node (ref "R11") (pin "2") (pinfunction "2_2") (pintype "passive"))
    )
    (net (code "53") (name "Net-(COILA-P)") (class "Default")
      (node (ref "C1") (pin "1") (pinfunction "1_1") (pintype "passive"))
      (node (ref "C2") (pin "1") (pinfunction "1_1") (pintype "passive"))
      (node (ref "C3") (pin "1") (pinfunction "1_1") (pintype "passive"))
      (node (ref "COILA") (pin "1") (pinfunction "P_1") (pintype "passive"))
      (node (ref "TP4") (pin "P$1") (pinfunction "P$1_P$1") (pintype "bidirectional"))
    )
    (net (code "54") (name "Net-(CSD25401Q3-G)") (class "Default")
      (node (ref "CSD25401Q3") (pin "4") (pinfunction "G_4") (pintype "passive"))
      (node (ref "FET_GATE") (pin "2") (pinfunction "2_2") (pintype "passive"))
    )
    (net (code "55") (name "Net-(IC1-FB)") (class "Default")
      (node (ref "IC1") (pin "10") (pinfunction "FB_10") (pintype "input"))
      (node (ref "R14") (pin "1") (pinfunction "1_1") (pintype "passive"))
      (node (ref "R17") (pin "1") (pinfunction "1_1") (pintype "passive"))
    )
    (net (code "56") (name "Net-(IC1-GND)") (class "Default")
      (node (ref "IC1") (pin "9") (pinfunction "GND_9") (pintype "power_in"))
      (node (ref "R14") (pin "2") (pinfunction "2_2") (pintype "passive"))
      (node (ref "R15") (pin "2") (pinfunction "2_2") (pintype "passive"))
    )
    (net (code "57") (name "Net-(IC1-L)") (class "Default")
      (node (ref "IC1") (pin "3") (pinfunction "L_3") (pintype "input"))
      (node (ref "L2") (pin "P$1") (pinfunction "1_P$1") (pintype "passive"))
    )
    (net (code "58") (name "Net-(IC1-UVLO)") (class "Default")
      (node (ref "C26") (pin "2") (pinfunction "2_2") (pintype "passive"))
      (node (ref "IC1") (pin "7") (pinfunction "UVLO_7") (pintype "input"))
      (node (ref "R15") (pin "1") (pinfunction "1_1") (pintype "passive"))
      (node (ref "R16") (pin "2") (pinfunction "2_2") (pintype "passive"))
    )
    (net (code "59") (name "Net-(IC1-VAUX)") (class "Default")
      (node (ref "C25") (pin "1") (pinfunction "1_1") (pintype "passive"))
      (node (ref "IC1") (pin "1") (pinfunction "VAUX_1") (pintype "bidirectional"))
    )
    (net (code "60") (name "Net-(IC1-VOUT)") (class "Default")
      (node (ref "IC1") (pin "2") (pinfunction "VOUT_2") (pintype "passive"))
      (node (ref "SJ4") (pin "1") (pinfunction "1_1") (pintype "passive"))
    )
    (net (code "61") (name "Net-(INT-PadA)") (class "Default")
      (node (ref "INT") (pin "A") (pinfunction "A_A") (pintype "passive"))
      (node (ref "R10") (pin "2") (pinfunction "2_2") (pintype "passive"))
    )
    (net (code "62") (name "Net-(QI+-PadA)") (class "Default")
      (node (ref "QI+") (pin "A") (pinfunction "A_A") (pintype "passive"))
      (node (ref "R2") (pin "1") (pinfunction "1_1") (pintype "passive"))
    )
    (net (code "63") (name "Net-(R9-A)") (class "Default")
      (node (ref "R9") (pin "1") (pinfunction "A_1") (pintype "passive"))
      (node (ref "TS") (pin "1") (pinfunction "1_1") (pintype "passive"))
    )
    (net (code "64") (name "Net-(TI_USB_MONITORB-KL)") (class "Default")
      (node (ref "R12") (pin "1") (pinfunction "1_1") (pintype "passive"))
      (node (ref "TI_USB_MONITOR") (pin "10") (pinfunction "KL_10") (pintype "passive"))
    )
    (net (code "65") (name "Net-(TI_USB_MONITORJ-KL)") (class "Default")
      (node (ref "R13") (pin "1") (pinfunction "1_1") (pintype "passive"))
      (node (ref "TI_USB_MONITOR") (pin "9") (pinfunction "KL_9") (pintype "passive"))
    )
    (net (code "66") (name "unconnected-(BQ24272-N.C.0-Pad1)") (class "Default")
      (node (ref "BQ24272") (pin "1") (pinfunction "N.C.0_1") (pintype "bidirectional"))
    )
    (net (code "67") (name "unconnected-(BQ24272-N.C.1-Pad2)") (class "Default")
      (node (ref "BQ24272") (pin "2") (pinfunction "N.C.1_2") (pintype "bidirectional"))
    )
    (net (code "68") (name "unconnected-(BQ51013AA-~{AD-EN}-Pad8)") (class "Default")
      (node (ref "BQ51013A") (pin "8") (pinfunction "~{AD-EN}_8") (pintype "bidirectional"))
    )
    (net (code "69") (name "unconnected-(TI_USB_MONITORA-KL-Pad1)") (class "Default")
      (node (ref "TI_USB_MONITOR") (pin "1") (pinfunction "KL_1") (pintype "passive"))
    )
    (net (code "70") (name "unconnected-(TI_USB_MONITORC-KL-Pad2)") (class "Default")
      (node (ref "TI_USB_MONITOR") (pin "2") (pinfunction "KL_2") (pintype "passive"))
    )
    (net (code "71") (name "unconnected-(TI_USB_MONITORD-KL-Pad3)") (class "Default")
      (node (ref "TI_USB_MONITOR") (pin "3") (pinfunction "KL_3") (pintype "passive"))
    )
    (net (code "72") (name "unconnected-(TI_USB_MONITORE-KL-Pad4)") (class "Default")
      (node (ref "TI_USB_MONITOR") (pin "4") (pinfunction "KL_4") (pintype "passive"))
    )
    (net (code "73") (name "unconnected-(TI_USB_MONITORF-KL-Pad5)") (class "Default")
      (node (ref "TI_USB_MONITOR") (pin "5") (pinfunction "KL_5") (pintype "passive"))
    )
    (net (code "74") (name "unconnected-(TI_USB_MONITORG-KL-Pad6)") (class "Default")
      (node (ref "TI_USB_MONITOR") (pin "6") (pinfunction "KL_6") (pintype "passive"))
    )
    (net (code "75") (name "unconnected-(TI_USB_MONITORI-KL-Pad8)") (class "Default")
      (node (ref "TI_USB_MONITOR") (pin "8") (pinfunction "KL_8") (pintype "passive"))
    )
    (net (code "76") (name "unconnected-(U$1-DNC-Pad4)") (class "Default")
      (node (ref "U$1") (pin "4") (pinfunction "DNC_4") (pintype "no_connect"))
    )
    (net (code "77") (name "unconnected-(U$1-DNC-Pad9)") (class "Default")
      (node (ref "U$1") (pin "9") (pinfunction "DNC_9") (pintype "no_connect"))
    )
    (net (code "78") (name "unconnected-(U$1-DNC-Pad14)") (class "Default")
      (node (ref "U$1") (pin "14") (pinfunction "DNC_14") (pintype "no_connect"))
    )
    (net (code "79") (name "unconnected-(U$1-DNC-Pad17)") (class "Default")
      (node (ref "U$1") (pin "17") (pinfunction "DNC_17") (pintype "no_connect"))
    )
    (net (code "80") (name "unconnected-(U$1-DNC-Pad20)") (class "Default")
      (node (ref "U$1") (pin "20") (pinfunction "DNC_20") (pintype "no_connect"))
    )
    (net (code "81") (name "unconnected-(U$1-DNC-Pad25)") (class "Default")
      (node (ref "U$1") (pin "25") (pinfunction "DNC_25") (pintype "no_connect"))
    )
    (net (code "82") (name "unconnected-(U$1-GPIO3-Pad15)") (class "Default")
      (node (ref "U$1") (pin "15") (pinfunction "GPIO3_15") (pintype "bidirectional"))
    )
  )
)
